# LED_Breakout_Board_V8.net
KiCad netlist of a schematic drawn in EAGLE
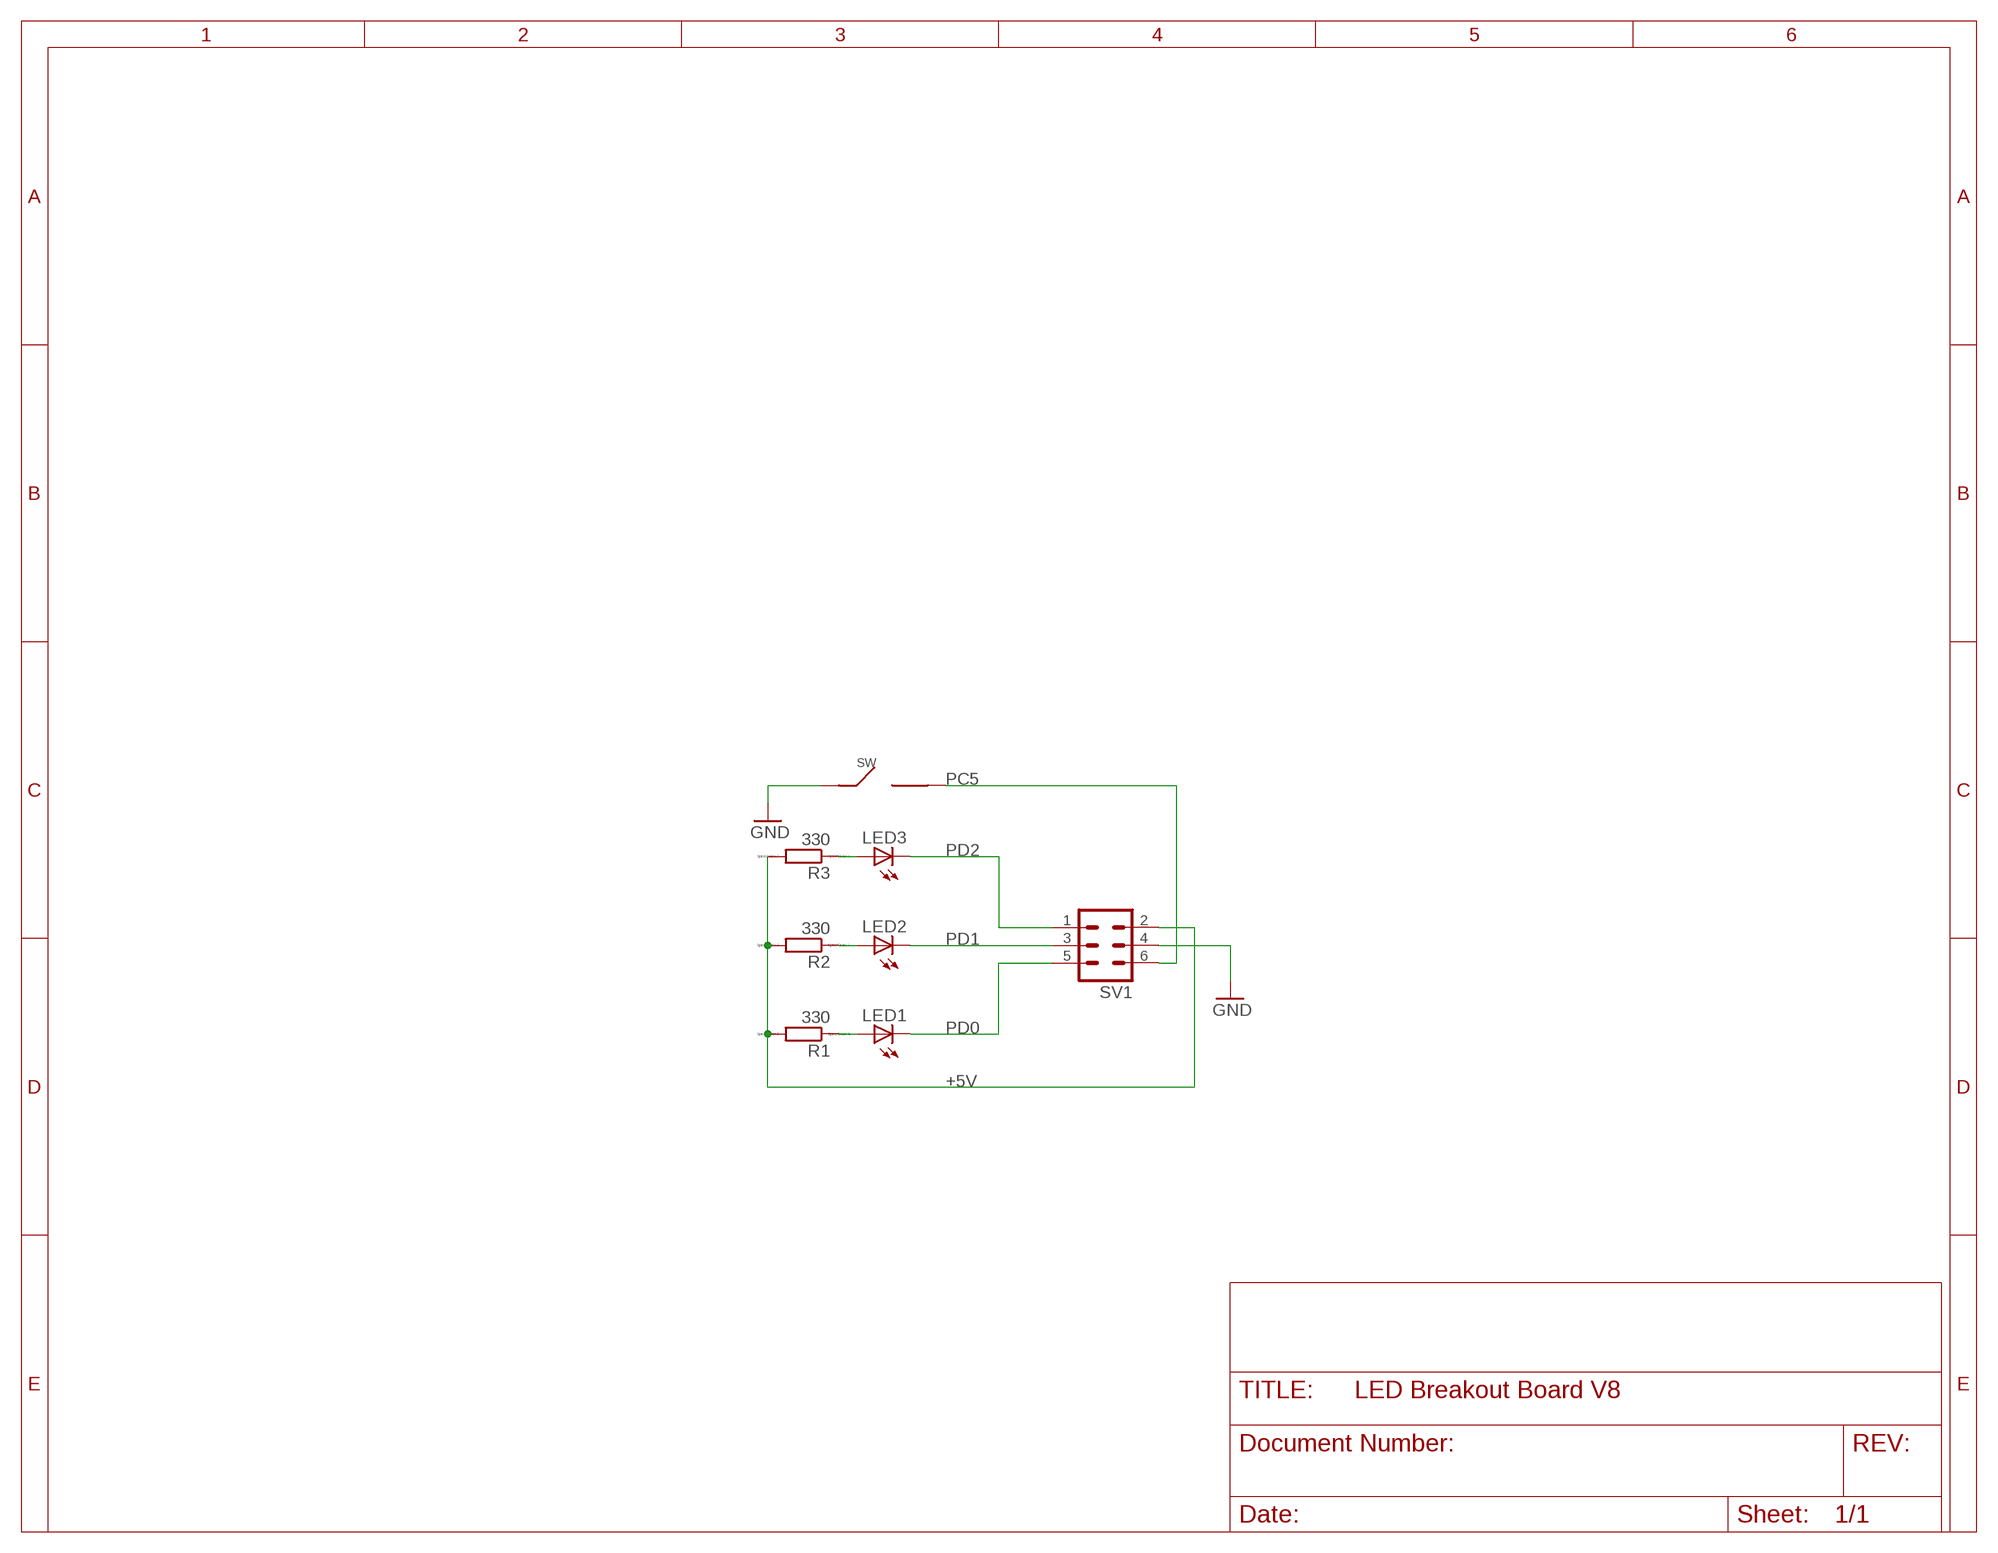
[diagram p0: schematic, sheet 1]

(export (version "E")
  (design (tool "Eeschema 10.0.6"))
  (components
    (comp (ref "LED1")
      (value "LED10MM")
      (footprint "eagle-import:LED10MM")
      (libsource (lib "eagle-import") (part "LED10MM"))
    )
    (comp (ref "LED2")
      (value "LED10MM")
      (footprint "eagle-import:LED10MM")
      (libsource (lib "eagle-import") (part "LED10MM"))
    )
    (comp (ref "LED3")
      (value "LED10MM")
      (footprint "eagle-import:LED10MM")
      (libsource (lib "eagle-import") (part "LED10MM"))
    )
    (comp (ref "R1")
      (value "330")
      (footprint "eagle-import:0207_10")
      (libsource (lib "eagle-import") (part "R0207/10"))
    )
    (comp (ref "R2")
      (value "330")
      (footprint "eagle-import:0207_10")
      (libsource (lib "eagle-import") (part "R0207/10"))
    )
    (comp (ref "R3")
      (value "330")
      (footprint "eagle-import:0207_10")
      (libsource (lib "eagle-import") (part "R0207/10"))
    )
    (comp (ref "SV1")
      (value "MA03-2")
      (footprint "eagle-import:MA03-2")
      (libsource (lib "eagle-import") (part "MA03-2"))
    )
    (comp (ref "SW")
      (value "PUSHBUTTON")
      (footprint "eagle-import:PUSHBUTTON")
      (libsource (lib "eagle-import") (part "PUSHBUTTON"))
    )
  )
  (nets
    (net (code "1") (name "/+5V") (class "Default")
      (node (ref "R1") (pin "2") (pinfunction "2_2") (pintype "passive"))
      (node (ref "R2") (pin "2") (pinfunction "2_2") (pintype "passive"))
      (node (ref "R3") (pin "2") (pinfunction "2_2") (pintype "passive"))
      (node (ref "SV1") (pin "2") (pinfunction "2_2") (pintype "passive"))
    )
    (net (code "2") (name "/PC5") (class "Default")
      (node (ref "SV1") (pin "6") (pinfunction "6_6") (pintype "passive"))
      (node (ref "SW") (pin "OUT") (pinfunction "OUT_OUT") (pintype "bidirectional"))
    )
    (net (code "3") (name "/PD0") (class "Default")
      (node (ref "LED1") (pin "K") (pinfunction "C_K") (pintype "passive"))
      (node (ref "SV1") (pin "5") (pinfunction "5_5") (pintype "passive"))
    )
    (net (code "4") (name "/PD1") (class "Default")
      (node (ref "LED2") (pin "K") (pinfunction "C_K") (pintype "passive"))
      (node (ref "SV1") (pin "3") (pinfunction "3_3") (pintype "passive"))
    )
    (net (code "5") (name "/PD2") (class "Default")
      (node (ref "LED3") (pin "K") (pinfunction "C_K") (pintype "passive"))
      (node (ref "SV1") (pin "1") (pinfunction "1_1") (pintype "passive"))
    )
    (net (code "6") (name "GND") (class "Default")
      (node (ref "SV1") (pin "4") (pinfunction "4_4") (pintype "passive"))
      (node (ref "SW") (pin "IN") (pinfunction "IN_IN") (pintype "bidirectional"))
    )
    (net (code "7") (name "Net-(LED1-PadA)") (class "Default")
      (node (ref "LED1") (pin "A") (pinfunction "A_A") (pintype "passive"))
      (node (ref "R1") (pin "1") (pinfunction "1_1") (pintype "passive"))
    )
    (net (code "8") (name "Net-(LED2-PadA)") (class "Default")
      (node (ref "LED2") (pin "A") (pinfunction "A_A") (pintype "passive"))
      (node (ref "R2") (pin "1") (pinfunction "1_1") (pintype "passive"))
    )
    (net (code "9") (name "Net-(LED3-PadA)") (class "Default")
      (node (ref "LED3") (pin "A") (pinfunction "A_A") (pintype "passive"))
      (node (ref "R3") (pin "1") (pinfunction "1_1") (pintype "passive"))
    )
  )
)
